# Schematico-amplificatore-audio.net
KiCad netlist of a schematic drawn in EAGLE
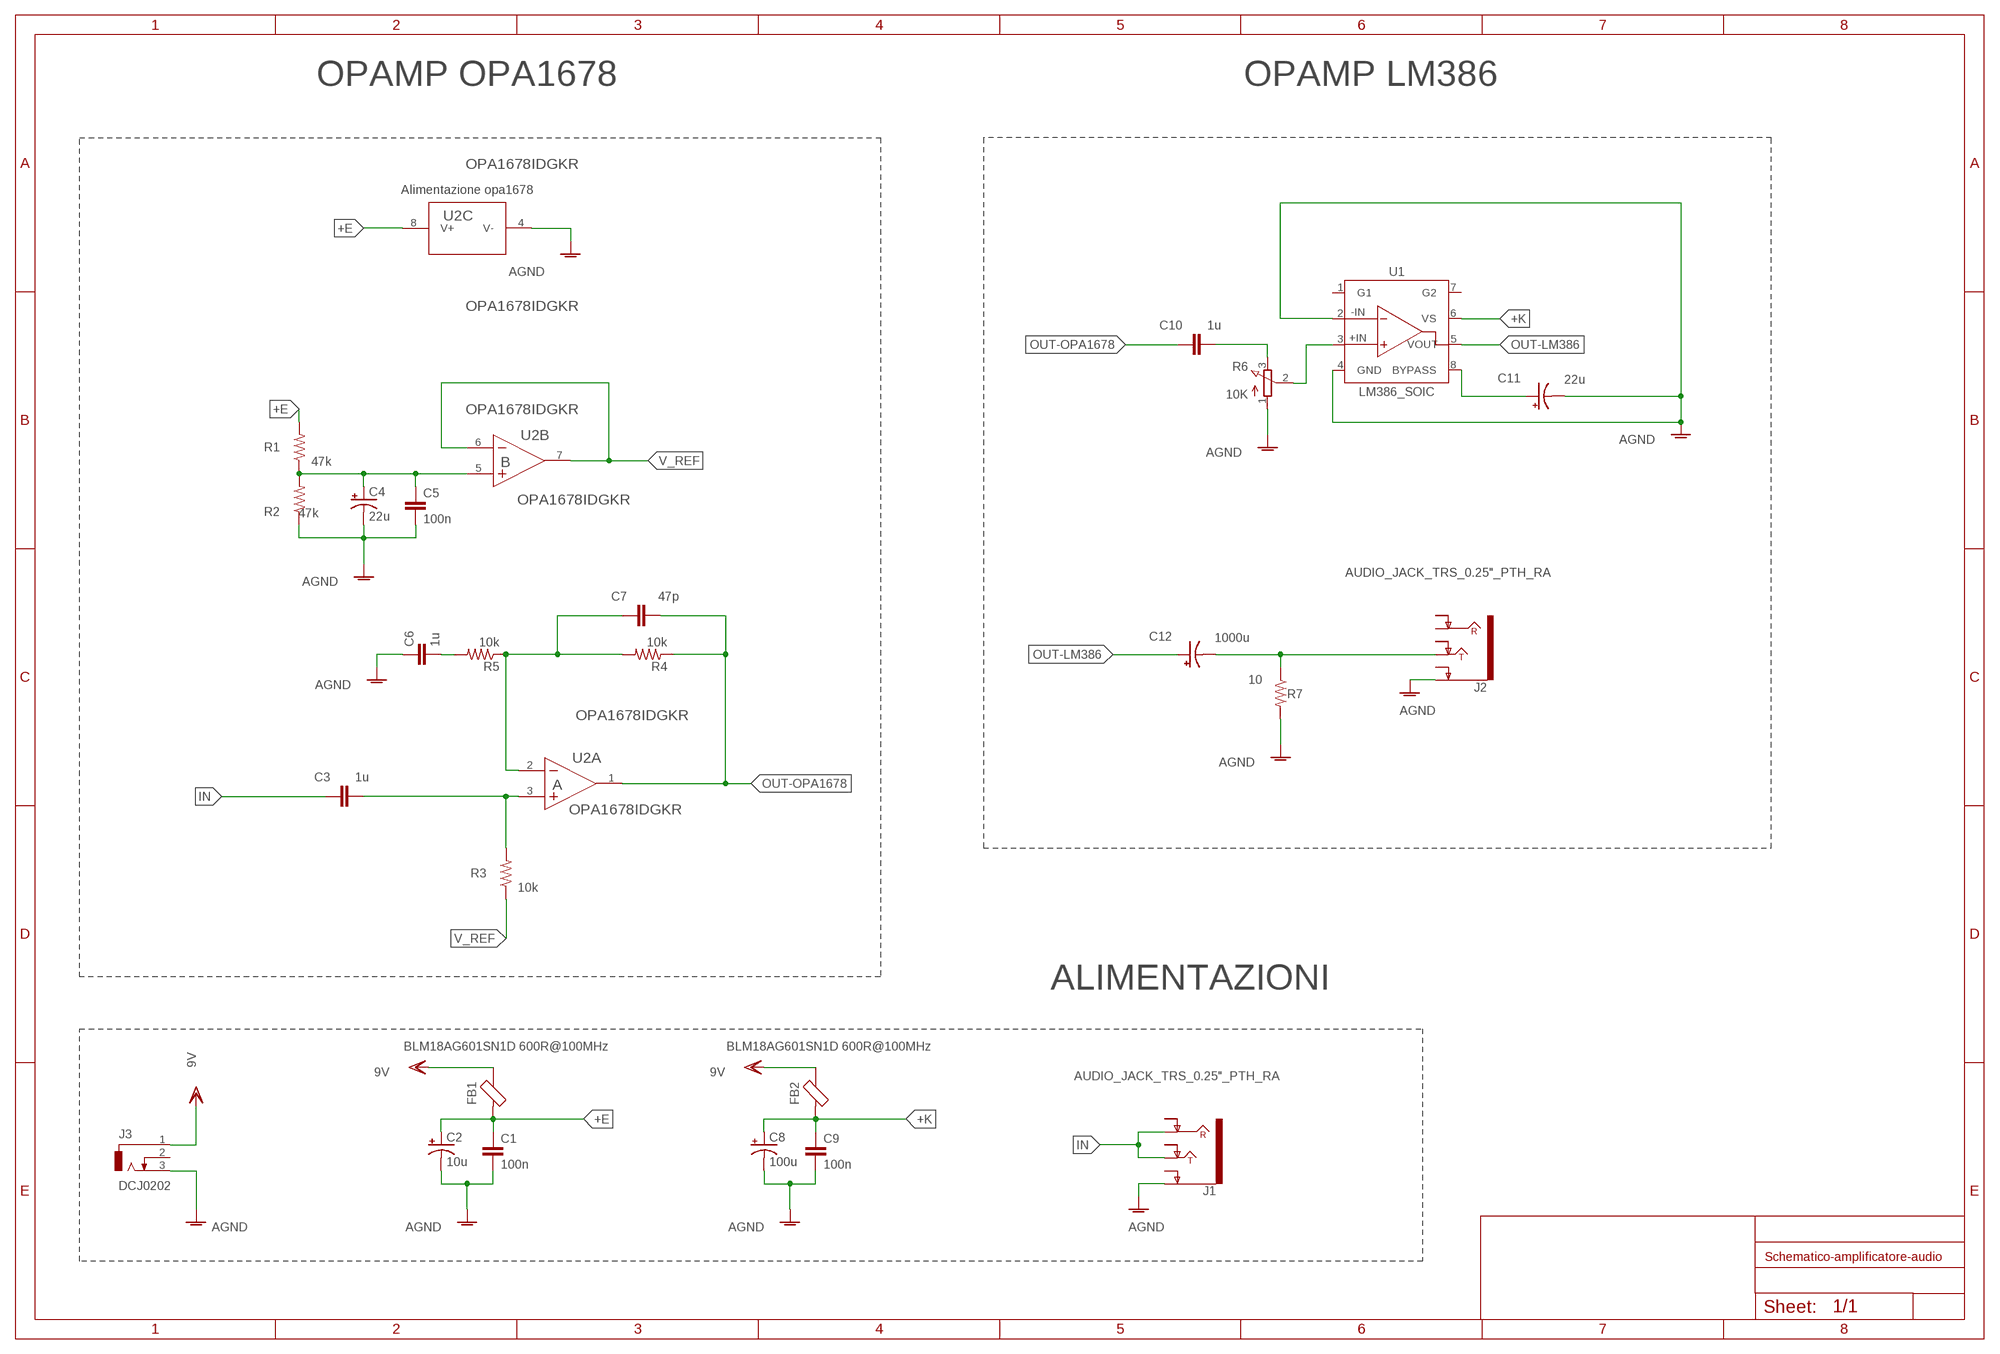
[diagram p0: schematic, sheet 1]

(export (version "E")
  (design (tool "Eeschema 10.0.6"))
  (components
    (comp (ref "C1")
      (value "100n")
      (footprint "eagle-import:C0603")
      (libsource (lib "eagle-import") (part "C-EUC0603"))
    )
    (comp (ref "C2")
      (value "10u")
      (footprint "eagle-import:CT3216")
      (libsource (lib "eagle-import") (part "CPOL-USCT3216"))
    )
    (comp (ref "C3")
      (value "1u")
      (footprint "eagle-import:C0603")
      (libsource (lib "eagle-import") (part "C-EUC0603"))
    )
    (comp (ref "C4")
      (value "22u")
      (footprint "eagle-import:CT3216")
      (libsource (lib "eagle-import") (part "CPOL-USCT3216"))
    )
    (comp (ref "C5")
      (value "100n")
      (footprint "eagle-import:C0603")
      (libsource (lib "eagle-import") (part "C-EUC0603"))
    )
    (comp (ref "C6")
      (value "1u")
      (footprint "eagle-import:C0603")
      (libsource (lib "eagle-import") (part "C-EUC0603"))
    )
    (comp (ref "C7")
      (value "47p")
      (footprint "eagle-import:C0603")
      (libsource (lib "eagle-import") (part "C-EUC0603"))
    )
    (comp (ref "C8")
      (value "100u")
      (footprint "eagle-import:CT3216")
      (libsource (lib "eagle-import") (part "CPOL-USCT3216"))
    )
    (comp (ref "C9")
      (value "100n")
      (footprint "eagle-import:C0603")
      (libsource (lib "eagle-import") (part "C-EUC0603"))
    )
    (comp (ref "C10")
      (value "1u")
      (footprint "eagle-import:C0603")
      (libsource (lib "eagle-import") (part "C-EUC0603"))
    )
    (comp (ref "C11")
      (value "22u")
      (footprint "eagle-import:CT3216")
      (libsource (lib "eagle-import") (part "CPOL-USCT3216"))
    )
    (comp (ref "C12")
      (value "1000u")
      (footprint "eagle-import:CT3216")
      (libsource (lib "eagle-import") (part "CPOL-USCT3216"))
    )
    (comp (ref "FB1")
      (value "BLM18AG601SN1D 600R@100MHz")
      (footprint "eagle-import:BEADC1608X95N")
      (fields (field (name "MANUFACTURER") "Murata Electronics") (field (name "MPN") "BLM18AG601SN1D"))
      (libsource (lib "eagle-import") (part "FB__0603(1608)BLM18AG601SN1D"))
    )
    (comp (ref "FB2")
      (value "BLM18AG601SN1D 600R@100MHz")
      (footprint "eagle-import:BEADC1608X95N")
      (fields (field (name "MANUFACTURER") "Murata Electronics") (field (name "MPN") "BLM18AG601SN1D"))
      (libsource (lib "eagle-import") (part "FB__0603(1608)BLM18AG601SN1D"))
    )
    (comp (ref "J1")
      (value "AUDIO_JACK_TRS_0.25\"_PTH_RA")
      (footprint "eagle-import:AUDIO_JACK_0.25__TRS_PTH_RA")
      (libsource (lib "eagle-import") (part "AUDIO_JACK_TRS_0.25{dblquote}_PTH_RA"))
    )
    (comp (ref "J2")
      (value "AUDIO_JACK_TRS_0.25\"_PTH_RA")
      (footprint "eagle-import:AUDIO_JACK_0.25__TRS_PTH_RA")
      (libsource (lib "eagle-import") (part "AUDIO_JACK_TRS_0.25{dblquote}_PTH_RA"))
    )
    (comp (ref "J3")
      (value "DCJ0202")
      (footprint "eagle-import:DCJ0202")
      (libsource (lib "eagle-import") (part "DCJ0202"))
    )
    (comp (ref "R1")
      (value "47k")
      (footprint "eagle-import:R0603")
      (libsource (lib "eagle-import") (part "R-US_R0603"))
    )
    (comp (ref "R2")
      (value "47k")
      (footprint "eagle-import:R0603")
      (libsource (lib "eagle-import") (part "R-US_R0603"))
    )
    (comp (ref "R3")
      (value "10k")
      (footprint "eagle-import:R0603")
      (libsource (lib "eagle-import") (part "R-US_R0603"))
    )
    (comp (ref "R4")
      (value "10k")
      (footprint "eagle-import:R0603")
      (libsource (lib "eagle-import") (part "R-US_R0603"))
    )
    (comp (ref "R5")
      (value "10k")
      (footprint "eagle-import:R0603")
      (libsource (lib "eagle-import") (part "R-US_R0603"))
    )
    (comp (ref "R6")
      (value "10K")
      (footprint "eagle-import:3RP_1610N")
      (libsource (lib "eagle-import") (part "3RP/1610N"))
    )
    (comp (ref "R7")
      (value "10")
      (footprint "eagle-import:R0603")
      (libsource (lib "eagle-import") (part "R-US_R0603"))
    )
    (comp (ref "U1")
      (value "LM386_SOIC")
      (footprint "eagle-import:SOIC127P600X175-8N")
      (libsource (lib "eagle-import") (part "LM386_SOIC"))
    )
    (comp (ref "U2")
      (value "OPA1678IDGKR")
      (footprint "eagle-import:DGK0008A_N")
      (fields (field (name "COPYRIGHT") "Copyright (C) 2026 Ultra Librarian. All rights reserved."))
      (libsource (lib "eagle-import") (part "OPA1678IDGKR"))
    )
  )
  (nets
    (net (code "1") (name "+E") (class "Default")
      (node (ref "C1") (pin "1") (pinfunction "1_1") (pintype "passive"))
      (node (ref "C2") (pin "+") (pinfunction "+_+") (pintype "passive"))
      (node (ref "FB1") (pin "1") (pinfunction "1_1") (pintype "passive"))
      (node (ref "R1") (pin "2") (pinfunction "2_2") (pintype "passive"))
      (node (ref "U2") (pin "8") (pinfunction "V+_8") (pintype "power_in"))
    )
    (net (code "2") (name "+K") (class "Default")
      (node (ref "C8") (pin "+") (pinfunction "+_+") (pintype "passive"))
      (node (ref "C9") (pin "1") (pinfunction "1_1") (pintype "passive"))
      (node (ref "FB2") (pin "1") (pinfunction "1_1") (pintype "passive"))
      (node (ref "U1") (pin "6") (pinfunction "VS_6") (pintype "bidirectional"))
    )
    (net (code "3") (name "9V") (class "Default")
      (node (ref "FB1") (pin "2") (pinfunction "2_2") (pintype "passive"))
      (node (ref "FB2") (pin "2") (pinfunction "2_2") (pintype "passive"))
      (node (ref "J3") (pin "1") (pinfunction "1_1") (pintype "passive"))
    )
    (net (code "4") (name "AGND") (class "Default")
      (node (ref "C1") (pin "2") (pinfunction "2_2") (pintype "passive"))
      (node (ref "C11") (pin "-") (pinfunction "-_-") (pintype "passive"))
      (node (ref "C2") (pin "-") (pinfunction "-_-") (pintype "passive"))
      (node (ref "C4") (pin "-") (pinfunction "-_-") (pintype "passive"))
      (node (ref "C5") (pin "2") (pinfunction "2_2") (pintype "passive"))
      (node (ref "C6") (pin "1") (pinfunction "1_1") (pintype "passive"))
      (node (ref "C8") (pin "-") (pinfunction "-_-") (pintype "passive"))
      (node (ref "C9") (pin "2") (pinfunction "2_2") (pintype "passive"))
      (node (ref "J1") (pin "SLEEVE") (pinfunction "EARTH_SLEEVE") (pintype "bidirectional"))
      (node (ref "J2") (pin "SLEEVE") (pinfunction "EARTH_SLEEVE") (pintype "bidirectional"))
      (node (ref "J3") (pin "3") (pinfunction "3_3") (pintype "passive"))
      (node (ref "R2") (pin "1") (pinfunction "1_1") (pintype "passive"))
      (node (ref "R6") (pin "1") (pinfunction "A_1") (pintype "passive"))
      (node (ref "R7") (pin "2") (pinfunction "2_2") (pintype "passive"))
      (node (ref "U1") (pin "2") (pinfunction "-IN_2") (pintype "input"))
      (node (ref "U1") (pin "4") (pinfunction "GND_4") (pintype "bidirectional"))
      (node (ref "U2") (pin "4") (pinfunction "V-_4") (pintype "power_in"))
    )
    (net (code "5") (name "IN") (class "Default")
      (node (ref "C3") (pin "1") (pinfunction "1_1") (pintype "passive"))
      (node (ref "J1") (pin "RING") (pinfunction "RING_RING") (pintype "bidirectional"))
      (node (ref "J1") (pin "TIP") (pinfunction "TIP_TIP") (pintype "bidirectional"))
    )
    (net (code "6") (name "Net-(C6-Pad2)") (class "Default")
      (node (ref "C6") (pin "2") (pinfunction "2_2") (pintype "passive"))
      (node (ref "R5") (pin "2") (pinfunction "2_2") (pintype "passive"))
    )
    (net (code "7") (name "Net-(C12-Pad-)") (class "Default")
      (node (ref "C12") (pin "-") (pinfunction "-_-") (pintype "passive"))
      (node (ref "J2") (pin "TIP") (pinfunction "TIP_TIP") (pintype "bidirectional"))
      (node (ref "R7") (pin "1") (pinfunction "1_1") (pintype "passive"))
    )
    (net (code "8") (name "Net-(R6-E)") (class "Default")
      (node (ref "C10") (pin "2") (pinfunction "2_2") (pintype "passive"))
      (node (ref "R6") (pin "3") (pinfunction "E_3") (pintype "passive"))
    )
    (net (code "9") (name "Net-(R6-S)") (class "Default")
      (node (ref "R6") (pin "2") (pinfunction "S_2") (pintype "passive"))
      (node (ref "U1") (pin "3") (pinfunction "+IN_3") (pintype "input"))
    )
    (net (code "10") (name "Net-(U1-BYPASS)") (class "Default")
      (node (ref "C11") (pin "+") (pinfunction "+_+") (pintype "passive"))
      (node (ref "U1") (pin "8") (pinfunction "BYPASS_8") (pintype "passive"))
    )
    (net (code "11") (name "Net-(U2A-IN+)") (class "Default")
      (node (ref "C3") (pin "2") (pinfunction "2_2") (pintype "passive"))
      (node (ref "R3") (pin "2") (pinfunction "2_2") (pintype "passive"))
      (node (ref "U2") (pin "3") (pinfunction "IN+_3") (pintype "input"))
    )
    (net (code "12") (name "Net-(U2A-IN-)") (class "Default")
      (node (ref "C7") (pin "1") (pinfunction "1_1") (pintype "passive"))
      (node (ref "R4") (pin "2") (pinfunction "2_2") (pintype "passive"))
      (node (ref "R5") (pin "1") (pinfunction "1_1") (pintype "passive"))
      (node (ref "U2") (pin "2") (pinfunction "IN-_2") (pintype "input"))
    )
    (net (code "13") (name "Net-(U2B-IN+)") (class "Default")
      (node (ref "C4") (pin "+") (pinfunction "+_+") (pintype "passive"))
      (node (ref "C5") (pin "1") (pinfunction "1_1") (pintype "passive"))
      (node (ref "R1") (pin "1") (pinfunction "1_1") (pintype "passive"))
      (node (ref "R2") (pin "2") (pinfunction "2_2") (pintype "passive"))
      (node (ref "U2") (pin "5") (pinfunction "IN+_5") (pintype "input"))
    )
    (net (code "14") (name "OUT-LM386") (class "Default")
      (node (ref "C12") (pin "+") (pinfunction "+_+") (pintype "passive"))
      (node (ref "U1") (pin "5") (pinfunction "VOUT_5") (pintype "output"))
    )
    (net (code "15") (name "OUT-OPA1678") (class "Default")
      (node (ref "C10") (pin "1") (pinfunction "1_1") (pintype "passive"))
      (node (ref "C7") (pin "2") (pinfunction "2_2") (pintype "passive"))
      (node (ref "R4") (pin "1") (pinfunction "1_1") (pintype "passive"))
      (node (ref "U2") (pin "1") (pinfunction "OUT_1") (pintype "output"))
    )
    (net (code "16") (name "V_REF") (class "Default")
      (node (ref "R3") (pin "1") (pinfunction "1_1") (pintype "passive"))
      (node (ref "U2") (pin "6") (pinfunction "IN-_6") (pintype "input"))
      (node (ref "U2") (pin "7") (pinfunction "OUT_7") (pintype "output"))
    )
    (net (code "17") (name "unconnected-(J1-EARTH-NORM-PadSLEEVE-NORM)") (class "Default")
      (node (ref "J1") (pin "SLEEVE-NORM") (pinfunction "EARTH-NORM_SLEEVE-NORM") (pintype "bidirectional"))
    )
    (net (code "18") (name "unconnected-(J1-PadRING-NORM)") (class "Default")
      (node (ref "J1") (pin "RING-NORM") (pinfunction "RING-NORM_RING-NORM") (pintype "bidirectional"))
    )
    (net (code "19") (name "unconnected-(J1-PadTIP-NORM)") (class "Default")
      (node (ref "J1") (pin "TIP-NORM") (pinfunction "TIP-NORM_TIP-NORM") (pintype "bidirectional"))
    )
    (net (code "20") (name "unconnected-(J2-EARTH-NORM-PadSLEEVE-NORM)") (class "Default")
      (node (ref "J2") (pin "SLEEVE-NORM") (pinfunction "EARTH-NORM_SLEEVE-NORM") (pintype "bidirectional"))
    )
    (net (code "21") (name "unconnected-(J2-PadRING)") (class "Default")
      (node (ref "J2") (pin "RING") (pinfunction "RING_RING") (pintype "bidirectional"))
    )
    (net (code "22") (name "unconnected-(J2-PadRING-NORM)") (class "Default")
      (node (ref "J2") (pin "RING-NORM") (pinfunction "RING-NORM_RING-NORM") (pintype "bidirectional"))
    )
    (net (code "23") (name "unconnected-(J2-PadTIP-NORM)") (class "Default")
      (node (ref "J2") (pin "TIP-NORM") (pinfunction "TIP-NORM_TIP-NORM") (pintype "bidirectional"))
    )
    (net (code "24") (name "unconnected-(J3-Pad2)") (class "Default")
      (node (ref "J3") (pin "2") (pinfunction "2_2") (pintype "passive"))
    )
    (net (code "25") (name "unconnected-(U1-G1-Pad1)") (class "Default")
      (node (ref "U1") (pin "1") (pinfunction "G1_1") (pintype "passive"))
    )
    (net (code "26") (name "unconnected-(U1-G2-Pad7)") (class "Default")
      (node (ref "U1") (pin "7") (pinfunction "G2_7") (pintype "passive"))
    )
  )
)
